# AFE.net
KiCad netlist of a schematic drawn in Altium Designer
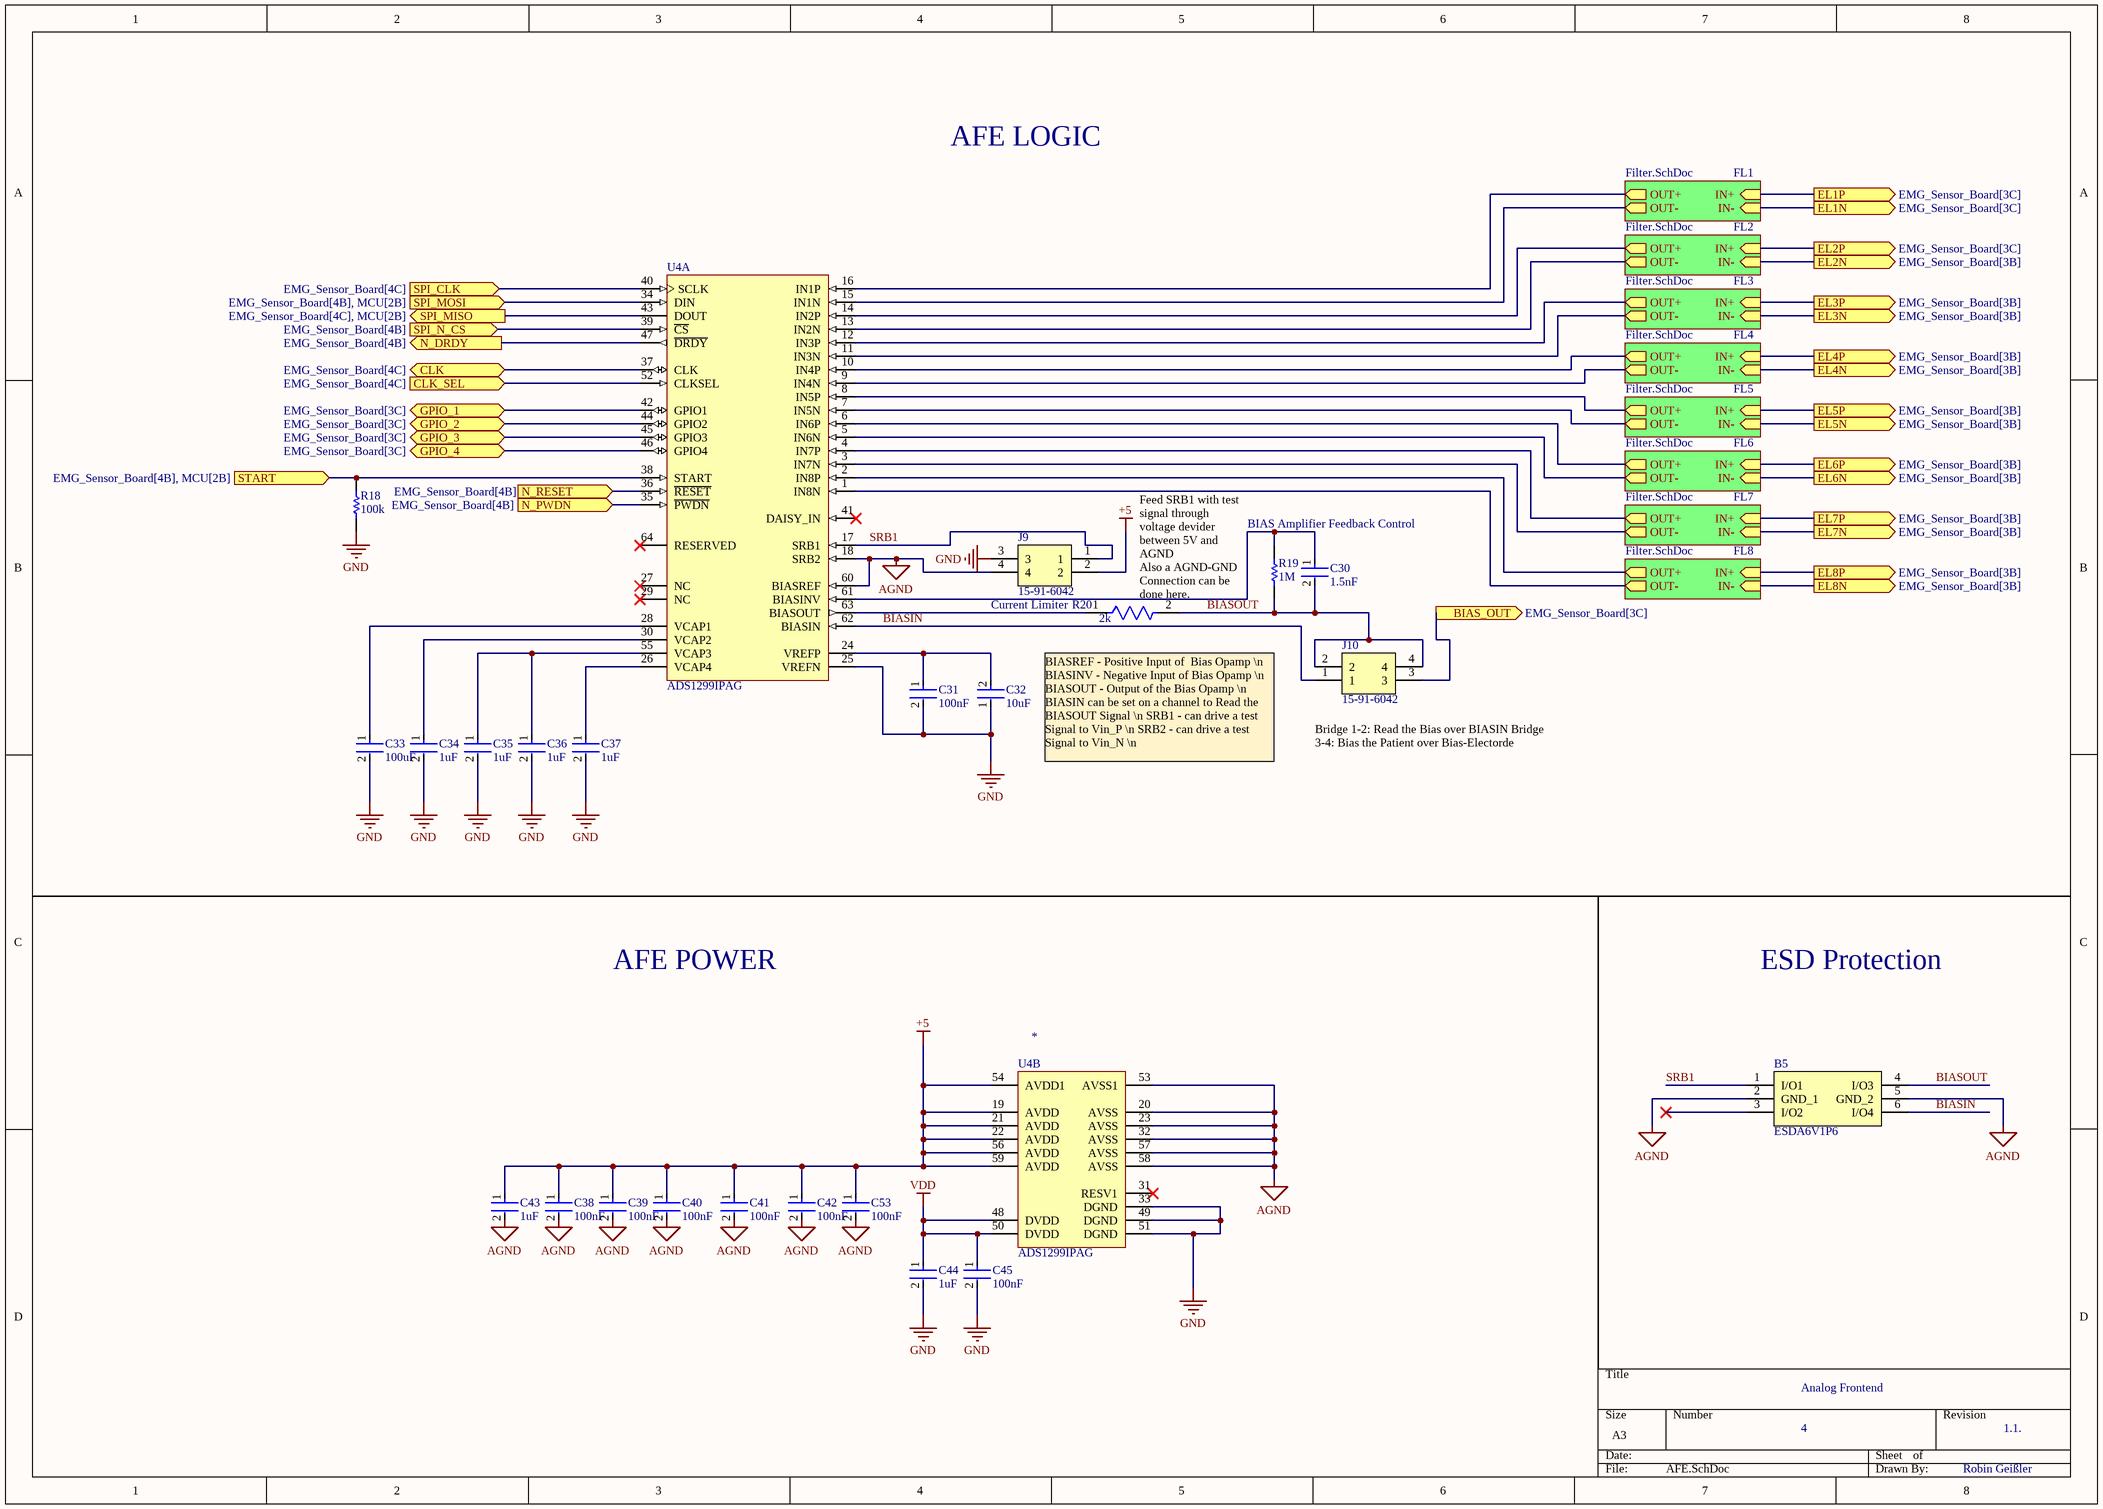
[diagram p0: AFE.SchDoc]

(export (version "E")
  (design (tool "Eeschema 10.0.6"))
  (components
    (comp (ref "B5")
      (value "ESDA6V1P6")
      (footprint "ESDA6V1P6")
      (description "4 line ESD protection, 6.1 V VBR, in SOT666")
      (fields (field (name "MOUSER PART NUMBER") "511-ESDA6V1P6"))
      (libsource (lib "EMG_Sensor") (part "ESDA6V1P6"))
    )
    (comp (ref "C30")
      (value "1.5nF")
      (footprint "FP-GRM188-0_1-e0_2_0_5-IPC_B")
      (description "Chip Multilayer Ceramic Capacitors for General Purpose, 0603, 1500pF, C0G, 30ppm/°C, 5%, 50V")
      (fields (field (name "TOLERANCE") "5%") (field (name "VOLTAGE") "50V"))
      (libsource (lib "Altium Content Vault") (part "11868f565c42a9108669ba33697ecf6"))
    )
    (comp (ref "C31")
      (value "100nF")
      (footprint "FP-CGA3E-0_3-0_1-IPC_A")
      (description "Cap Ceramic 100nF 50V X7R 10% Pad SMD 0603 +125°C Automotive T/R")
      (fields (field (name "TOLERANCE") "10%") (field (name "VOLTAGE") "50V"))
      (libsource (lib "Altium Content Vault") (part "b4654b650e69147ec39a6b967a45e02"))
    )
    (comp (ref "C32")
      (value "10uF")
      (footprint "FP-C1608-080-0_1-MFG")
      (description "Multilayer Ceramic Capacitors 10μF ±10% 10V X5R SMD 0603")
      (fields (field (name "VOLTAGE") "10V") (field (name "TOLERANCE") "10%"))
      (libsource (lib "Altium Content Vault") (part "236180d848d6139a670b325ea6854c9"))
    )
    (comp (ref "C33")
      (value "100uF")
      (footprint "FP-C4532-280-0_4-IPC_B")
      (description "CAP CER 100UF 6.3V X6S 1812")
      (fields (field (name "TOLERANCE") "20%"))
      (libsource (lib "Altium Content Vault") (part "02cd4be3c70576c341d710602a673aa"))
    )
    (comp (ref "C34")
      (value "1uF")
      (footprint "FP-CGA3E-0_3-0_1-IPC_B")
      (description "Cap Ceramic 1uF 35V X7R 10% Pad SMD 0603 +125°C Automotive T/R")
      (fields (field (name "TOLERANCE") "10%"))
      (libsource (lib "Altium Content Vault") (part "b4654b650e69147ec39a6b967a45e02"))
    )
    (comp (ref "C35")
      (value "1uF")
      (footprint "FP-CGA3E-0_3-0_1-IPC_B")
      (description "Cap Ceramic 1uF 35V X7R 10% Pad SMD 0603 +125°C Automotive T/R")
      (fields (field (name "TOLERANCE") "10%"))
      (libsource (lib "Altium Content Vault") (part "b4654b650e69147ec39a6b967a45e02"))
    )
    (comp (ref "C36")
      (value "1uF")
      (footprint "FP-CGA3E-0_3-0_1-IPC_B")
      (description "Cap Ceramic 1uF 35V X7R 10% Pad SMD 0603 +125°C Automotive T/R")
      (fields (field (name "TOLERANCE") "10%"))
      (libsource (lib "Altium Content Vault") (part "b4654b650e69147ec39a6b967a45e02"))
    )
    (comp (ref "C37")
      (value "1uF")
      (footprint "FP-CGA3E-0_3-0_1-IPC_B")
      (description "Cap Ceramic 1uF 35V X7R 10% Pad SMD 0603 +125°C Automotive T/R")
      (fields (field (name "TOLERANCE") "10%"))
      (libsource (lib "Altium Content Vault") (part "b4654b650e69147ec39a6b967a45e02"))
    )
    (comp (ref "C38")
      (value "100nF")
      (footprint "FP-CGA3E-0_3-0_1-IPC_A")
      (description "Cap Ceramic 100nF 50V X7R 10% Pad SMD 0603 +125°C Automotive T/R")
      (fields (field (name "TOLERANCE") "10%") (field (name "VOLTAGE") "50V"))
      (libsource (lib "Altium Content Vault") (part "b4654b650e69147ec39a6b967a45e02"))
    )
    (comp (ref "C39")
      (value "100nF")
      (footprint "FP-CGA3E-0_3-0_1-IPC_A")
      (description "Cap Ceramic 100nF 50V X7R 10% Pad SMD 0603 +125°C Automotive T/R")
      (fields (field (name "TOLERANCE") "10%") (field (name "VOLTAGE") "50V"))
      (libsource (lib "Altium Content Vault") (part "b4654b650e69147ec39a6b967a45e02"))
    )
    (comp (ref "C40")
      (value "100nF")
      (footprint "FP-CGA3E-0_3-0_1-IPC_A")
      (description "Cap Ceramic 100nF 50V X7R 10% Pad SMD 0603 +125°C Automotive T/R")
      (fields (field (name "TOLERANCE") "10%") (field (name "VOLTAGE") "50V"))
      (libsource (lib "Altium Content Vault") (part "b4654b650e69147ec39a6b967a45e02"))
    )
    (comp (ref "C41")
      (value "100nF")
      (footprint "FP-CGA3E-0_3-0_1-IPC_A")
      (description "Cap Ceramic 100nF 50V X7R 10% Pad SMD 0603 +125°C Automotive T/R")
      (fields (field (name "TOLERANCE") "10%") (field (name "VOLTAGE") "50V"))
      (libsource (lib "Altium Content Vault") (part "b4654b650e69147ec39a6b967a45e02"))
    )
    (comp (ref "C42")
      (value "100nF")
      (footprint "FP-CGA3E-0_3-0_1-IPC_A")
      (description "Cap Ceramic 100nF 50V X7R 10% Pad SMD 0603 +125°C Automotive T/R")
      (fields (field (name "TOLERANCE") "10%") (field (name "VOLTAGE") "50V"))
      (libsource (lib "Altium Content Vault") (part "b4654b650e69147ec39a6b967a45e02"))
    )
    (comp (ref "C43")
      (value "1uF")
      (footprint "FP-CGA3E-0_3-0_1-IPC_B")
      (description "Cap Ceramic 1uF 35V X7R 10% Pad SMD 0603 +125°C Automotive T/R")
      (fields (field (name "TOLERANCE") "10%"))
      (libsource (lib "Altium Content Vault") (part "b4654b650e69147ec39a6b967a45e02"))
    )
    (comp (ref "C44")
      (value "1uF")
      (footprint "FP-CGA3E-0_3-0_1-IPC_B")
      (description "Cap Ceramic 1uF 35V X7R 10% Pad SMD 0603 +125°C Automotive T/R")
      (fields (field (name "TOLERANCE") "10%"))
      (libsource (lib "Altium Content Vault") (part "b4654b650e69147ec39a6b967a45e02"))
    )
    (comp (ref "C45")
      (value "100nF")
      (footprint "FP-CGA3E-0_3-0_1-IPC_A")
      (description "Cap Ceramic 100nF 50V X7R 10% Pad SMD 0603 +125°C Automotive T/R")
      (fields (field (name "TOLERANCE") "10%") (field (name "VOLTAGE") "50V"))
      (libsource (lib "Altium Content Vault") (part "b4654b650e69147ec39a6b967a45e02"))
    )
    (comp (ref "C53")
      (value "100nF")
      (footprint "FP-CGA3E-0_3-0_1-IPC_A")
      (description "Cap Ceramic 100nF 50V X7R 10% Pad SMD 0603 +125°C Automotive T/R")
      (fields (field (name "TOLERANCE") "10%") (field (name "VOLTAGE") "50V"))
      (libsource (lib "Altium Content Vault") (part "b4654b650e69147ec39a6b967a45e02"))
    )
    (comp (ref "J9")
      (value "15-91-6042")
      (footprint "15916042")
      (fields (field (name "MOUSER PART NUMBER") "538-15-91-6042"))
      (libsource (lib "EMG_Sensor") (part "15-91-6042"))
    )
    (comp (ref "J10")
      (value "15-91-6042")
      (footprint "15916042")
      (fields (field (name "MOUSER PART NUMBER") "538-15-91-6042"))
      (libsource (lib "") (part "15-91-6042_1"))
    )
    (comp (ref "R18")
      (value "100k")
      (footprint "RESC1609X55X30ML10T20")
      (description "TNPW0603100KBEEA")
      (fields (field (name "MANUFACTURER") "Vishay Dale"))
      (libsource (lib "Altium Content Vault") (part "RES"))
    )
    (comp (ref "R19")
      (value "1M")
      (footprint "RESC1608X55X25LL10T15")
      (description "Chip Resistor, 1 MOhm, +/- 1%, 100 mW, -55 to 155 degC, 0603 (1608 Metric), RoHS, Tape and Reel")
      (fields (field (name "TOLERANCE") "20%"))
      (libsource (lib "Altium Content Vault") (part "RES-2"))
    )
    (comp (ref "R20")
      (value "2k")
      (footprint "FP-ERA3A-IPC_C")
      (description "RES SMD 2K OHM 0.1% 1/10W 0603")
      (fields (field (name "TOLERANCE") "0.1%"))
      (libsource (lib "Altium Content Vault") (part "1029c3af85768c4190bb7ad29bc67b5"))
    )
    (comp (ref "U4")
      (value "ADS1299IPAG")
      (footprint "PAG0064A_N")
      (fields (field (name "MANUFACTURER") "Texas Instruments"))
      (libsource (lib "Altium Content Vault") (part "TI-ADS1299-PAG-64"))
    )
  )
  (nets
    (net (code "1") (name "+5") (class "Default")
      (node (ref "C38") (pin "1") (pinfunction "1_1") (pintype "passive"))
      (node (ref "C39") (pin "1") (pinfunction "1_1") (pintype "passive"))
      (node (ref "C40") (pin "1") (pinfunction "1_1") (pintype "passive"))
      (node (ref "C41") (pin "1") (pinfunction "1_1") (pintype "passive"))
      (node (ref "C42") (pin "1") (pinfunction "1_1") (pintype "passive"))
      (node (ref "C43") (pin "1") (pinfunction "1_1") (pintype "passive"))
      (node (ref "C53") (pin "1") (pinfunction "1_1") (pintype "passive"))
      (node (ref "J9") (pin "2") (pinfunction "2_2") (pintype "passive"))
      (node (ref "U4") (pin "19") (pinfunction "AVDD_19") (pintype "power_in"))
      (node (ref "U4") (pin "21") (pinfunction "AVDD_21") (pintype "power_in"))
      (node (ref "U4") (pin "22") (pinfunction "AVDD_22") (pintype "power_in"))
      (node (ref "U4") (pin "54") (pinfunction "AVDD1_54") (pintype "power_in"))
      (node (ref "U4") (pin "56") (pinfunction "AVDD_56") (pintype "power_in"))
      (node (ref "U4") (pin "59") (pinfunction "AVDD_59") (pintype "power_in"))
    )
    (net (code "2") (name "/BIASIN") (class "Default")
      (node (ref "B5") (pin "6") (pinfunction "I/O4_6") (pintype "passive"))
      (node (ref "J10") (pin "1") (pinfunction "1_1") (pintype "passive"))
      (node (ref "U4") (pin "62") (pinfunction "BIASIN_62") (pintype "input"))
    )
    (net (code "3") (name "/BIASOUT") (class "Default")
      (node (ref "B5") (pin "4") (pinfunction "I/O3_4") (pintype "passive"))
      (node (ref "C30") (pin "2") (pinfunction "2_2") (pintype "passive"))
      (node (ref "J10") (pin "2") (pinfunction "2_2") (pintype "passive"))
      (node (ref "J10") (pin "4") (pinfunction "4_4") (pintype "passive"))
      (node (ref "R19") (pin "1") (pinfunction "1_1") (pintype "passive"))
      (node (ref "R20") (pin "2") (pinfunction "2_2") (pintype "passive"))
    )
    (net (code "4") (name "/BIAS_OUT") (class "Default")
      (node (ref "J10") (pin "3") (pinfunction "3_3") (pintype "passive"))
    )
    (net (code "5") (name "/CLK") (class "Default")
      (node (ref "U4") (pin "37") (pinfunction "CLK_37") (pintype "bidirectional"))
    )
    (net (code "6") (name "/CLK_SEL") (class "Default")
      (node (ref "U4") (pin "52") (pinfunction "CLKSEL_52") (pintype "input"))
    )
    (net (code "23") (name "/GPIO_1") (class "Default")
      (node (ref "U4") (pin "42") (pinfunction "GPIO1_42") (pintype "bidirectional"))
    )
    (net (code "24") (name "/GPIO_2") (class "Default")
      (node (ref "U4") (pin "44") (pinfunction "GPIO2_44") (pintype "bidirectional"))
    )
    (net (code "25") (name "/GPIO_3") (class "Default")
      (node (ref "U4") (pin "45") (pinfunction "GPIO3_45") (pintype "bidirectional"))
    )
    (net (code "26") (name "/GPIO_4") (class "Default")
      (node (ref "U4") (pin "46") (pinfunction "GPIO4_46") (pintype "bidirectional"))
    )
    (net (code "27") (name "/N_DRDY") (class "Default")
      (node (ref "U4") (pin "47") (pinfunction "~{DRDY}_47") (pintype "output"))
    )
    (net (code "28") (name "/N_PWDN") (class "Default")
      (node (ref "U4") (pin "35") (pinfunction "~{PWDN}_35") (pintype "input"))
    )
    (net (code "29") (name "/N_RESET") (class "Default")
      (node (ref "U4") (pin "36") (pinfunction "~{RESET}_36") (pintype "input"))
    )
    (net (code "30") (name "/OUT+") (class "Default")
      (node (ref "U4") (pin "2") (pinfunction "IN8P_2") (pintype "input"))
    )
    (net (code "31") (name "/OUT+_1") (class "Default")
      (node (ref "U4") (pin "16") (pinfunction "IN1P_16") (pintype "input"))
    )
    (net (code "32") (name "/OUT+_2") (class "Default")
      (node (ref "U4") (pin "14") (pinfunction "IN2P_14") (pintype "input"))
    )
    (net (code "33") (name "/OUT+_3") (class "Default")
      (node (ref "U4") (pin "12") (pinfunction "IN3P_12") (pintype "input"))
    )
    (net (code "34") (name "/OUT+_4") (class "Default")
      (node (ref "U4") (pin "10") (pinfunction "IN4P_10") (pintype "input"))
    )
    (net (code "35") (name "/OUT+_5") (class "Default")
      (node (ref "U4") (pin "8") (pinfunction "IN5P_8") (pintype "input"))
    )
    (net (code "36") (name "/OUT+_6") (class "Default")
      (node (ref "U4") (pin "6") (pinfunction "IN6P_6") (pintype "input"))
    )
    (net (code "37") (name "/OUT+_7") (class "Default")
      (node (ref "U4") (pin "4") (pinfunction "IN7P_4") (pintype "input"))
    )
    (net (code "38") (name "/OUT-") (class "Default")
      (node (ref "U4") (pin "1") (pinfunction "IN8N_1") (pintype "input"))
    )
    (net (code "39") (name "/OUT-_1") (class "Default")
      (node (ref "U4") (pin "15") (pinfunction "IN1N_15") (pintype "input"))
    )
    (net (code "40") (name "/OUT-_2") (class "Default")
      (node (ref "U4") (pin "13") (pinfunction "IN2N_13") (pintype "input"))
    )
    (net (code "41") (name "/OUT-_3") (class "Default")
      (node (ref "U4") (pin "11") (pinfunction "IN3N_11") (pintype "input"))
    )
    (net (code "42") (name "/OUT-_4") (class "Default")
      (node (ref "U4") (pin "9") (pinfunction "IN4N_9") (pintype "input"))
    )
    (net (code "43") (name "/OUT-_5") (class "Default")
      (node (ref "U4") (pin "7") (pinfunction "IN5N_7") (pintype "input"))
    )
    (net (code "44") (name "/OUT-_6") (class "Default")
      (node (ref "U4") (pin "5") (pinfunction "IN6N_5") (pintype "input"))
    )
    (net (code "45") (name "/OUT-_7") (class "Default")
      (node (ref "U4") (pin "3") (pinfunction "IN7N_3") (pintype "input"))
    )
    (net (code "46") (name "/SPI_CLK") (class "Default")
      (node (ref "U4") (pin "40") (pinfunction "SCLK_40") (pintype "input"))
    )
    (net (code "47") (name "/SPI_MISO") (class "Default")
      (node (ref "U4") (pin "43") (pinfunction "DOUT_43") (pintype "tri_state"))
    )
    (net (code "48") (name "/SPI_MOSI") (class "Default")
      (node (ref "U4") (pin "34") (pinfunction "DIN_34") (pintype "input"))
    )
    (net (code "49") (name "/SPI_N_CS") (class "Default")
      (node (ref "U4") (pin "39") (pinfunction "~{CS}_39") (pintype "input"))
    )
    (net (code "50") (name "/SRB1") (class "Default")
      (node (ref "B5") (pin "1") (pinfunction "I/O1_1") (pintype "passive"))
      (node (ref "J9") (pin "1") (pinfunction "1_1") (pintype "passive"))
      (node (ref "U4") (pin "17") (pinfunction "SRB1_17") (pintype "input"))
    )
    (net (code "51") (name "/START") (class "Default")
      (node (ref "R18") (pin "2") (pinfunction "2_2") (pintype "passive"))
      (node (ref "U4") (pin "38") (pinfunction "START_38") (pintype "input"))
    )
    (net (code "52") (name "AGND") (class "Default")
      (node (ref "B5") (pin "2") (pinfunction "GND_1_2") (pintype "passive"))
      (node (ref "B5") (pin "5") (pinfunction "GND_2_5") (pintype "passive"))
      (node (ref "C38") (pin "2") (pinfunction "2_2") (pintype "passive"))
      (node (ref "C39") (pin "2") (pinfunction "2_2") (pintype "passive"))
      (node (ref "C40") (pin "2") (pinfunction "2_2") (pintype "passive"))
      (node (ref "C41") (pin "2") (pinfunction "2_2") (pintype "passive"))
      (node (ref "C42") (pin "2") (pinfunction "2_2") (pintype "passive"))
      (node (ref "C43") (pin "2") (pinfunction "2_2") (pintype "passive"))
      (node (ref "C53") (pin "2") (pinfunction "2_2") (pintype "passive"))
      (node (ref "J9") (pin "4") (pinfunction "4_4") (pintype "passive"))
      (node (ref "U4") (pin "18") (pinfunction "SRB2_18") (pintype "input"))
      (node (ref "U4") (pin "20") (pinfunction "AVSS_20") (pintype "power_in"))
      (node (ref "U4") (pin "23") (pinfunction "AVSS_23") (pintype "power_in"))
      (node (ref "U4") (pin "32") (pinfunction "AVSS_32") (pintype "power_in"))
      (node (ref "U4") (pin "53") (pinfunction "AVSS1_53") (pintype "power_in"))
      (node (ref "U4") (pin "57") (pinfunction "AVSS_57") (pintype "power_in"))
      (node (ref "U4") (pin "58") (pinfunction "AVSS_58") (pintype "power_in"))
      (node (ref "U4") (pin "60") (pinfunction "BIASREF_60") (pintype "input"))
    )
    (net (code "53") (name "GND") (class "Default")
      (node (ref "C31") (pin "2") (pinfunction "2_2") (pintype "passive"))
      (node (ref "C32") (pin "1") (pinfunction "1_1") (pintype "passive"))
      (node (ref "C33") (pin "2") (pinfunction "2_2") (pintype "passive"))
      (node (ref "C34") (pin "2") (pinfunction "2_2") (pintype "passive"))
      (node (ref "C35") (pin "2") (pinfunction "2_2") (pintype "passive"))
      (node (ref "C36") (pin "2") (pinfunction "2_2") (pintype "passive"))
      (node (ref "C37") (pin "2") (pinfunction "2_2") (pintype "passive"))
      (node (ref "C44") (pin "2") (pinfunction "2_2") (pintype "passive"))
      (node (ref "C45") (pin "2") (pinfunction "2_2") (pintype "passive"))
      (node (ref "J9") (pin "3") (pinfunction "3_3") (pintype "passive"))
      (node (ref "R18") (pin "1") (pinfunction "1_1") (pintype "passive"))
      (node (ref "U4") (pin "25") (pinfunction "VREFN_25") (pintype "passive"))
      (node (ref "U4") (pin "33") (pinfunction "DGND_33") (pintype "power_in"))
      (node (ref "U4") (pin "49") (pinfunction "DGND_49") (pintype "power_in"))
      (node (ref "U4") (pin "51") (pinfunction "DGND_51") (pintype "power_in"))
    )
    (net (code "54") (name "Net-(U4A-BIASINV)") (class "Default")
      (node (ref "C30") (pin "1") (pinfunction "1_1") (pintype "passive"))
      (node (ref "R19") (pin "2") (pinfunction "2_2") (pintype "passive"))
      (node (ref "U4") (pin "61") (pinfunction "BIASINV_61") (pintype "input"))
    )
    (net (code "55") (name "Net-(U4A-BIASOUT)") (class "Default")
      (node (ref "R20") (pin "1") (pinfunction "1_1") (pintype "passive"))
      (node (ref "U4") (pin "63") (pinfunction "BIASOUT_63") (pintype "output"))
    )
    (net (code "56") (name "Net-(U4A-VCAP1)") (class "Default")
      (node (ref "C33") (pin "1") (pinfunction "1_1") (pintype "passive"))
      (node (ref "U4") (pin "28") (pinfunction "VCAP1_28") (pintype "passive"))
    )
    (net (code "57") (name "Net-(U4A-VCAP2)") (class "Default")
      (node (ref "C34") (pin "1") (pinfunction "1_1") (pintype "passive"))
      (node (ref "U4") (pin "30") (pinfunction "VCAP2_30") (pintype "passive"))
    )
    (net (code "58") (name "Net-(U4A-VCAP3)") (class "Default")
      (node (ref "C35") (pin "1") (pinfunction "1_1") (pintype "passive"))
      (node (ref "C36") (pin "1") (pinfunction "1_1") (pintype "passive"))
      (node (ref "U4") (pin "55") (pinfunction "VCAP3_55") (pintype "passive"))
    )
    (net (code "59") (name "Net-(U4A-VCAP4)") (class "Default")
      (node (ref "C37") (pin "1") (pinfunction "1_1") (pintype "passive"))
      (node (ref "U4") (pin "26") (pinfunction "VCAP4_26") (pintype "passive"))
    )
    (net (code "60") (name "Net-(U4A-VREFP)") (class "Default")
      (node (ref "C31") (pin "1") (pinfunction "1_1") (pintype "passive"))
      (node (ref "C32") (pin "2") (pinfunction "2_2") (pintype "passive"))
      (node (ref "U4") (pin "24") (pinfunction "VREFP_24") (pintype "passive"))
    )
    (net (code "61") (name "VDD") (class "Default")
      (node (ref "C44") (pin "1") (pinfunction "1_1") (pintype "passive"))
      (node (ref "C45") (pin "1") (pinfunction "1_1") (pintype "passive"))
      (node (ref "U4") (pin "48") (pinfunction "DVDD_48") (pintype "power_in"))
      (node (ref "U4") (pin "50") (pinfunction "DVDD_50") (pintype "power_in"))
    )
    (net (code "62") (name "unconnected-(B5-I{slash}O2-Pad3)") (class "Default")
      (node (ref "B5") (pin "3") (pinfunction "I/O2_3") (pintype "passive+no_connect"))
    )
    (net (code "63") (name "unconnected-(U4A-DAISY_IN-Pad41)") (class "Default")
      (node (ref "U4") (pin "41") (pinfunction "DAISY_IN_41") (pintype "input+no_connect"))
    )
    (net (code "64") (name "unconnected-(U4A-NC-Pad27)") (class "Default")
      (node (ref "U4") (pin "27") (pinfunction "NC_27") (pintype "passive+no_connect"))
    )
    (net (code "65") (name "unconnected-(U4A-NC-Pad29)") (class "Default")
      (node (ref "U4") (pin "29") (pinfunction "NC_29") (pintype "passive+no_connect"))
    )
    (net (code "66") (name "unconnected-(U4A-RESERVED-Pad64)") (class "Default")
      (node (ref "U4") (pin "64") (pinfunction "RESERVED_64") (pintype "passive+no_connect"))
    )
    (net (code "67") (name "unconnected-(U4B-RESV1-Pad31)") (class "Default")
      (node (ref "U4") (pin "31") (pinfunction "RESV1_31") (pintype "power_in+no_connect"))
    )
  )
)
